# SimpleCART.net
KiCad netlist of a schematic drawn in EAGLE
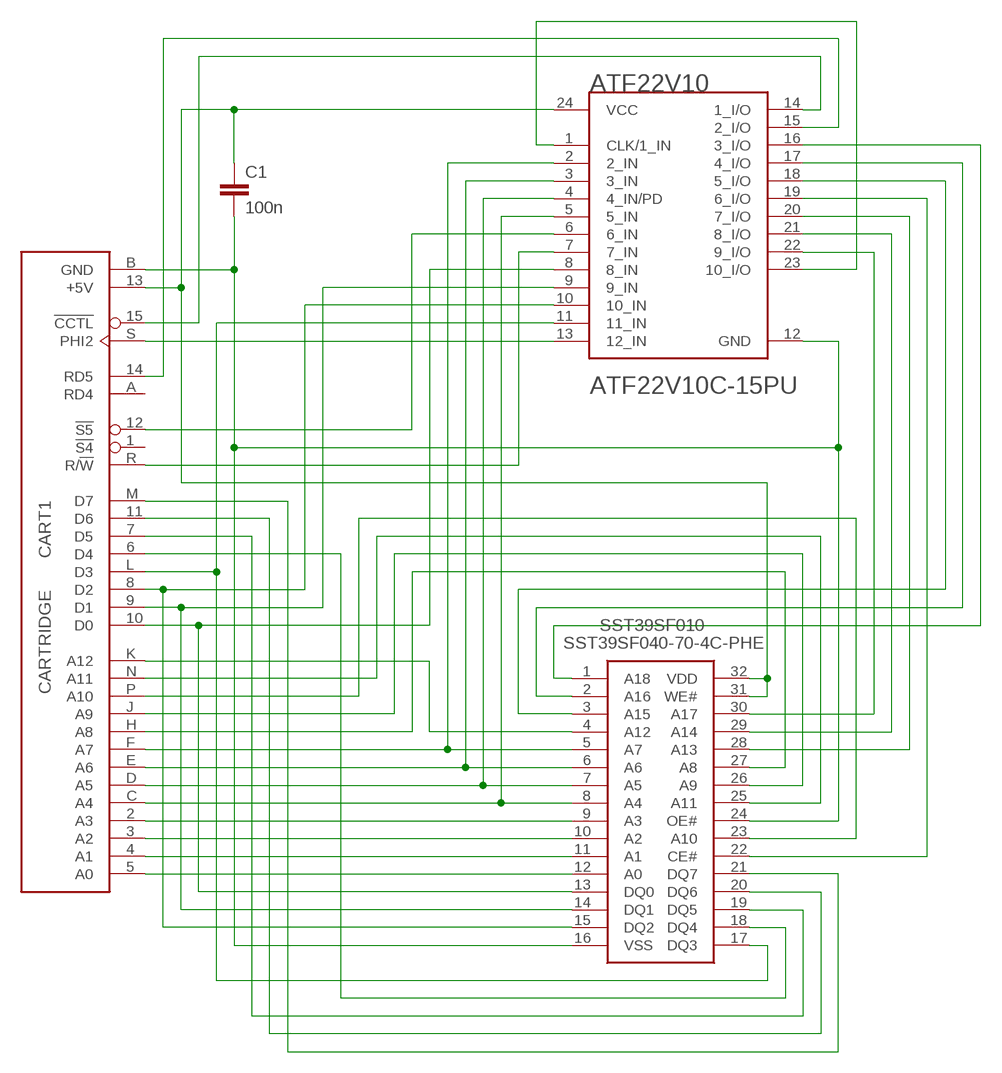
[diagram p0: schematic, sheet 1]

(export (version "E")
  (design (tool "Eeschema 10.0.6"))
  (components
    (comp (ref "ATF22V10")
      (value "MICROCHIP_ATF22V10C-15PUMICROCHIP_ATF22V10C-15PU_0_0")
      (footprint "eagle-import:MICROCHIP_ATF22V10C-15PU_0")
      (fields
        (field (name "DIGIKEY_PART_NUMBER") "ATF22V10C-15PU-ND")
        (field (name "MF") "Microchip")
        (field (name "MOUSER_PART_NUMBER") "556-AF22V10C15PU")
      )
      (libsource (lib "eagle-import") (part "MICROCHIP_ATF22V10C-15PUMICROCHIP_ATF22V10C-15PU_0_0"))
    )
    (comp (ref "C1")
      (value "100n")
      (footprint "eagle-import:C025-024X044")
      (libsource (lib "eagle-import") (part "C-EU025-024X044"))
    )
    (comp (ref "CART1")
      (value "CARTRIDGE")
      (footprint "eagle-import:CARTRIDGE")
      (libsource (lib "eagle-import") (part "CARTRIDGE"))
    )
    (comp (ref "SST39SF010")
      (value "SST39SF040-70-4C-PHE")
      (footprint "eagle-import:DIP1556W56P254L4191H508Q32N")
      (fields (field (name "MOUSER_PART_NUMBER") "804-39SF0407CPHE"))
      (libsource (lib "eagle-import") (part "SST39SF040-70-4C-PHE"))
    )
  )
  (nets
    (net (code "1") (name "Net-(ATF22V10-1_I{slash}O)") (class "Default")
      (node (ref "ATF22V10") (pin "14") (pinfunction "1_I/O_14") (pintype "bidirectional"))
      (node (ref "CART1") (pin "15") (pinfunction "~{CCTL}_15") (pintype "output"))
    )
    (net (code "2") (name "Net-(ATF22V10-2_IN)") (class "Default")
      (node (ref "ATF22V10") (pin "2") (pinfunction "2_IN_2") (pintype "input"))
      (node (ref "CART1") (pin "F") (pinfunction "A7_F") (pintype "output"))
      (node (ref "SST39SF010") (pin "5") (pinfunction "A7_5") (pintype "bidirectional"))
    )
    (net (code "3") (name "Net-(ATF22V10-2_I{slash}O)") (class "Default")
      (node (ref "ATF22V10") (pin "15") (pinfunction "2_I/O_15") (pintype "bidirectional"))
      (node (ref "CART1") (pin "14") (pinfunction "RD5_14") (pintype "input"))
    )
    (net (code "4") (name "Net-(ATF22V10-3_IN)") (class "Default")
      (node (ref "ATF22V10") (pin "3") (pinfunction "3_IN_3") (pintype "input"))
      (node (ref "CART1") (pin "E") (pinfunction "A6_E") (pintype "output"))
      (node (ref "SST39SF010") (pin "6") (pinfunction "A6_6") (pintype "bidirectional"))
    )
    (net (code "5") (name "Net-(ATF22V10-3_I{slash}O)") (class "Default")
      (node (ref "ATF22V10") (pin "16") (pinfunction "3_I/O_16") (pintype "bidirectional"))
      (node (ref "SST39SF010") (pin "1") (pinfunction "A18_1") (pintype "bidirectional"))
    )
    (net (code "6") (name "Net-(ATF22V10-4_IN{slash}PD)") (class "Default")
      (node (ref "ATF22V10") (pin "4") (pinfunction "4_IN/PD_4") (pintype "input"))
      (node (ref "CART1") (pin "D") (pinfunction "A5_D") (pintype "output"))
      (node (ref "SST39SF010") (pin "7") (pinfunction "A5_7") (pintype "bidirectional"))
    )
    (net (code "7") (name "Net-(ATF22V10-4_I{slash}O)") (class "Default")
      (node (ref "ATF22V10") (pin "17") (pinfunction "4_I/O_17") (pintype "bidirectional"))
      (node (ref "SST39SF010") (pin "2") (pinfunction "A16_2") (pintype "bidirectional"))
    )
    (net (code "8") (name "Net-(ATF22V10-5_IN)") (class "Default")
      (node (ref "ATF22V10") (pin "5") (pinfunction "5_IN_5") (pintype "input"))
      (node (ref "CART1") (pin "C") (pinfunction "A4_C") (pintype "output"))
      (node (ref "SST39SF010") (pin "8") (pinfunction "A4_8") (pintype "bidirectional"))
    )
    (net (code "9") (name "Net-(ATF22V10-5_I{slash}O)") (class "Default")
      (node (ref "ATF22V10") (pin "18") (pinfunction "5_I/O_18") (pintype "bidirectional"))
      (node (ref "SST39SF010") (pin "3") (pinfunction "A15_3") (pintype "bidirectional"))
    )
    (net (code "10") (name "Net-(ATF22V10-6_IN)") (class "Default")
      (node (ref "ATF22V10") (pin "6") (pinfunction "6_IN_6") (pintype "input"))
      (node (ref "CART1") (pin "12") (pinfunction "~{S5}_12") (pintype "output"))
    )
    (net (code "11") (name "Net-(ATF22V10-6_I{slash}O)") (class "Default")
      (node (ref "ATF22V10") (pin "19") (pinfunction "6_I/O_19") (pintype "bidirectional"))
      (node (ref "SST39SF010") (pin "22") (pinfunction "CE#_22") (pintype "bidirectional"))
    )
    (net (code "12") (name "Net-(ATF22V10-7_IN)") (class "Default")
      (node (ref "ATF22V10") (pin "7") (pinfunction "7_IN_7") (pintype "input"))
      (node (ref "CART1") (pin "R") (pinfunction "R/~{W}_R") (pintype "output"))
    )
    (net (code "13") (name "Net-(ATF22V10-7_I{slash}O)") (class "Default")
      (node (ref "ATF22V10") (pin "20") (pinfunction "7_I/O_20") (pintype "bidirectional"))
      (node (ref "SST39SF010") (pin "28") (pinfunction "A13_28") (pintype "bidirectional"))
    )
    (net (code "14") (name "Net-(ATF22V10-8_IN)") (class "Default")
      (node (ref "ATF22V10") (pin "8") (pinfunction "8_IN_8") (pintype "input"))
      (node (ref "CART1") (pin "10") (pinfunction "D0_10") (pintype "bidirectional"))
      (node (ref "SST39SF010") (pin "13") (pinfunction "DQ0_13") (pintype "bidirectional"))
    )
    (net (code "15") (name "Net-(ATF22V10-8_I{slash}O)") (class "Default")
      (node (ref "ATF22V10") (pin "21") (pinfunction "8_I/O_21") (pintype "bidirectional"))
      (node (ref "SST39SF010") (pin "29") (pinfunction "A14_29") (pintype "bidirectional"))
    )
    (net (code "16") (name "Net-(ATF22V10-9_IN)") (class "Default")
      (node (ref "ATF22V10") (pin "9") (pinfunction "9_IN_9") (pintype "input"))
      (node (ref "CART1") (pin "9") (pinfunction "D1_9") (pintype "bidirectional"))
      (node (ref "SST39SF010") (pin "14") (pinfunction "DQ1_14") (pintype "bidirectional"))
    )
    (net (code "17") (name "Net-(ATF22V10-9_I{slash}O)") (class "Default")
      (node (ref "ATF22V10") (pin "22") (pinfunction "9_I/O_22") (pintype "bidirectional"))
      (node (ref "SST39SF010") (pin "30") (pinfunction "A17_30") (pintype "bidirectional"))
    )
    (net (code "18") (name "Net-(ATF22V10-10_IN)") (class "Default")
      (node (ref "ATF22V10") (pin "10") (pinfunction "10_IN_10") (pintype "input"))
      (node (ref "CART1") (pin "8") (pinfunction "D2_8") (pintype "bidirectional"))
      (node (ref "SST39SF010") (pin "15") (pinfunction "DQ2_15") (pintype "bidirectional"))
    )
    (net (code "19") (name "Net-(ATF22V10-10_I{slash}O)") (class "Default")
      (node (ref "ATF22V10") (pin "1") (pinfunction "CLK/1_IN_1") (pintype "input"))
      (node (ref "ATF22V10") (pin "23") (pinfunction "10_I/O_23") (pintype "bidirectional"))
    )
    (net (code "20") (name "Net-(ATF22V10-11_IN)") (class "Default")
      (node (ref "ATF22V10") (pin "11") (pinfunction "11_IN_11") (pintype "input"))
      (node (ref "CART1") (pin "L") (pinfunction "D3_L") (pintype "bidirectional"))
      (node (ref "SST39SF010") (pin "17") (pinfunction "DQ3_17") (pintype "bidirectional"))
    )
    (net (code "21") (name "Net-(ATF22V10-12_IN)") (class "Default")
      (node (ref "ATF22V10") (pin "13") (pinfunction "12_IN_13") (pintype "input"))
      (node (ref "CART1") (pin "S") (pinfunction "PHI2_S") (pintype "output"))
    )
    (net (code "22") (name "Net-(ATF22V10-GND)") (class "Default")
      (node (ref "ATF22V10") (pin "12") (pinfunction "GND_12") (pintype "power_in"))
      (node (ref "C1") (pin "2") (pinfunction "2_2") (pintype "passive"))
      (node (ref "CART1") (pin "B") (pinfunction "GND_B") (pintype "power_in"))
      (node (ref "SST39SF010") (pin "16") (pinfunction "VSS_16") (pintype "bidirectional"))
      (node (ref "SST39SF010") (pin "24") (pinfunction "OE#_24") (pintype "bidirectional"))
    )
    (net (code "23") (name "Net-(ATF22V10-VCC)") (class "Default")
      (node (ref "ATF22V10") (pin "24") (pinfunction "VCC_24") (pintype "power_in"))
      (node (ref "C1") (pin "1") (pinfunction "1_1") (pintype "passive"))
      (node (ref "CART1") (pin "13") (pinfunction "+5V_13") (pintype "power_in"))
      (node (ref "SST39SF010") (pin "31") (pinfunction "WE#_31") (pintype "bidirectional"))
      (node (ref "SST39SF010") (pin "32") (pinfunction "VDD_32") (pintype "bidirectional"))
    )
    (net (code "24") (name "Net-(CART1-A0)") (class "Default")
      (node (ref "CART1") (pin "5") (pinfunction "A0_5") (pintype "output"))
      (node (ref "SST39SF010") (pin "12") (pinfunction "A0_12") (pintype "bidirectional"))
    )
    (net (code "25") (name "Net-(CART1-A1)") (class "Default")
      (node (ref "CART1") (pin "4") (pinfunction "A1_4") (pintype "output"))
      (node (ref "SST39SF010") (pin "11") (pinfunction "A1_11") (pintype "bidirectional"))
    )
    (net (code "26") (name "Net-(CART1-A2)") (class "Default")
      (node (ref "CART1") (pin "3") (pinfunction "A2_3") (pintype "output"))
      (node (ref "SST39SF010") (pin "10") (pinfunction "A2_10") (pintype "bidirectional"))
    )
    (net (code "27") (name "Net-(CART1-A3)") (class "Default")
      (node (ref "CART1") (pin "2") (pinfunction "A3_2") (pintype "output"))
      (node (ref "SST39SF010") (pin "9") (pinfunction "A3_9") (pintype "bidirectional"))
    )
    (net (code "28") (name "Net-(CART1-A8)") (class "Default")
      (node (ref "CART1") (pin "H") (pinfunction "A8_H") (pintype "output"))
      (node (ref "SST39SF010") (pin "27") (pinfunction "A8_27") (pintype "bidirectional"))
    )
    (net (code "29") (name "Net-(CART1-A9)") (class "Default")
      (node (ref "CART1") (pin "J") (pinfunction "A9_J") (pintype "output"))
      (node (ref "SST39SF010") (pin "26") (pinfunction "A9_26") (pintype "bidirectional"))
    )
    (net (code "30") (name "Net-(CART1-A10)") (class "Default")
      (node (ref "CART1") (pin "P") (pinfunction "A10_P") (pintype "output"))
      (node (ref "SST39SF010") (pin "23") (pinfunction "A10_23") (pintype "bidirectional"))
    )
    (net (code "31") (name "Net-(CART1-A11)") (class "Default")
      (node (ref "CART1") (pin "N") (pinfunction "A11_N") (pintype "output"))
      (node (ref "SST39SF010") (pin "25") (pinfunction "A11_25") (pintype "bidirectional"))
    )
    (net (code "32") (name "Net-(CART1-A12)") (class "Default")
      (node (ref "CART1") (pin "K") (pinfunction "A12_K") (pintype "output"))
      (node (ref "SST39SF010") (pin "4") (pinfunction "A12_4") (pintype "bidirectional"))
    )
    (net (code "33") (name "Net-(CART1-D4)") (class "Default")
      (node (ref "CART1") (pin "6") (pinfunction "D4_6") (pintype "bidirectional"))
      (node (ref "SST39SF010") (pin "18") (pinfunction "DQ4_18") (pintype "bidirectional"))
    )
    (net (code "34") (name "Net-(CART1-D5)") (class "Default")
      (node (ref "CART1") (pin "7") (pinfunction "D5_7") (pintype "bidirectional"))
      (node (ref "SST39SF010") (pin "19") (pinfunction "DQ5_19") (pintype "bidirectional"))
    )
    (net (code "35") (name "Net-(CART1-D6)") (class "Default")
      (node (ref "CART1") (pin "11") (pinfunction "D6_11") (pintype "bidirectional"))
      (node (ref "SST39SF010") (pin "20") (pinfunction "DQ6_20") (pintype "bidirectional"))
    )
    (net (code "36") (name "Net-(CART1-D7)") (class "Default")
      (node (ref "CART1") (pin "M") (pinfunction "D7_M") (pintype "bidirectional"))
      (node (ref "SST39SF010") (pin "21") (pinfunction "DQ7_21") (pintype "bidirectional"))
    )
    (net (code "37") (name "unconnected-(CART1-RD4-PadA)") (class "Default")
      (node (ref "CART1") (pin "A") (pinfunction "RD4_A") (pintype "input"))
    )
    (net (code "38") (name "unconnected-(CART1-~{S4}-Pad1)") (class "Default")
      (node (ref "CART1") (pin "1") (pinfunction "~{S4}_1") (pintype "output"))
    )
  )
)
